# 20200805.net
KiCad netlist of a schematic drawn in Altium Designer
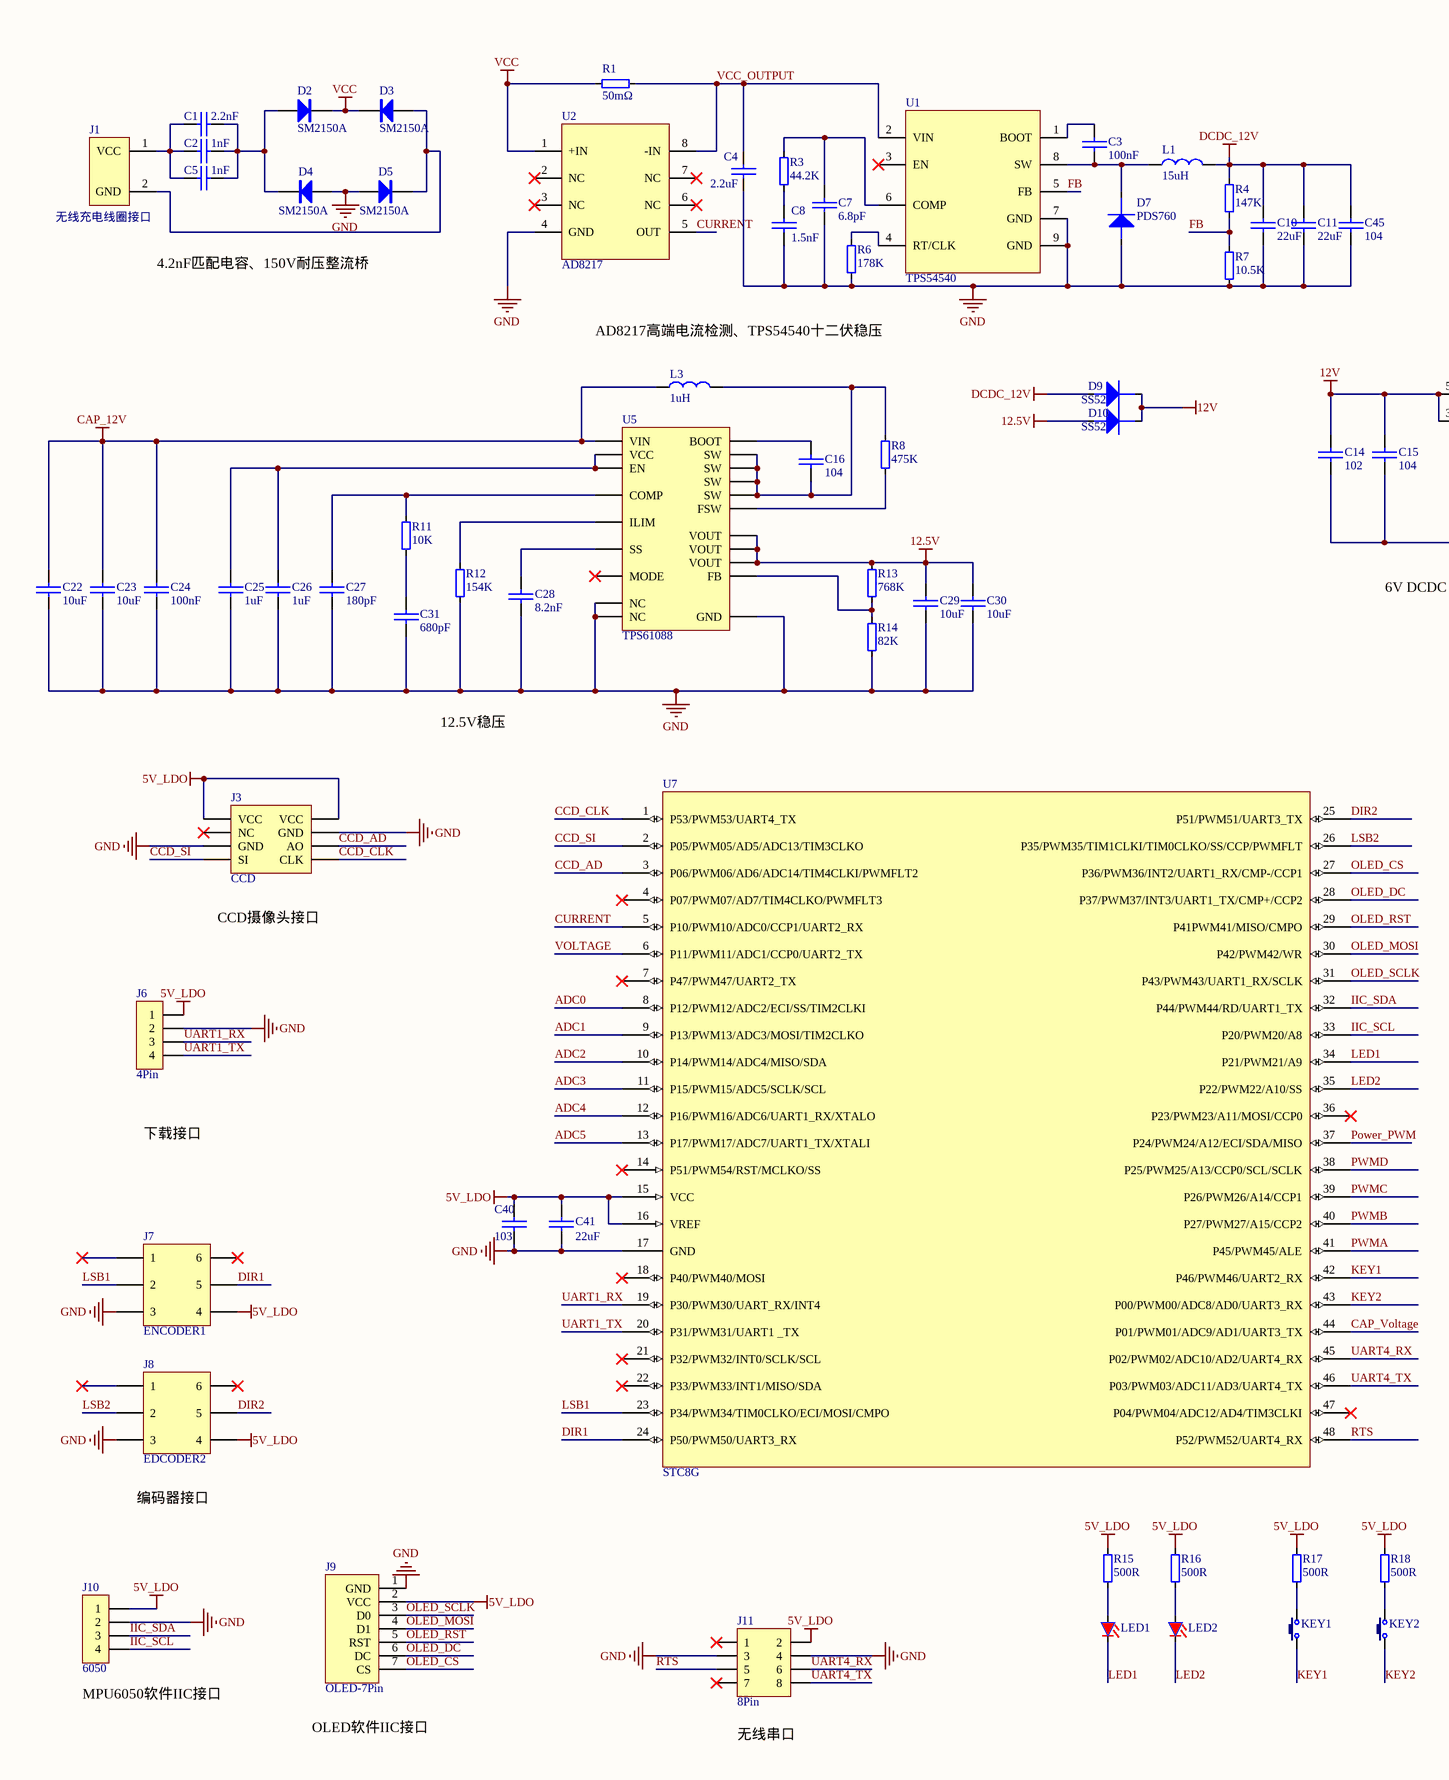
[diagram p0: 驰风队20200805.SchDoc, left]
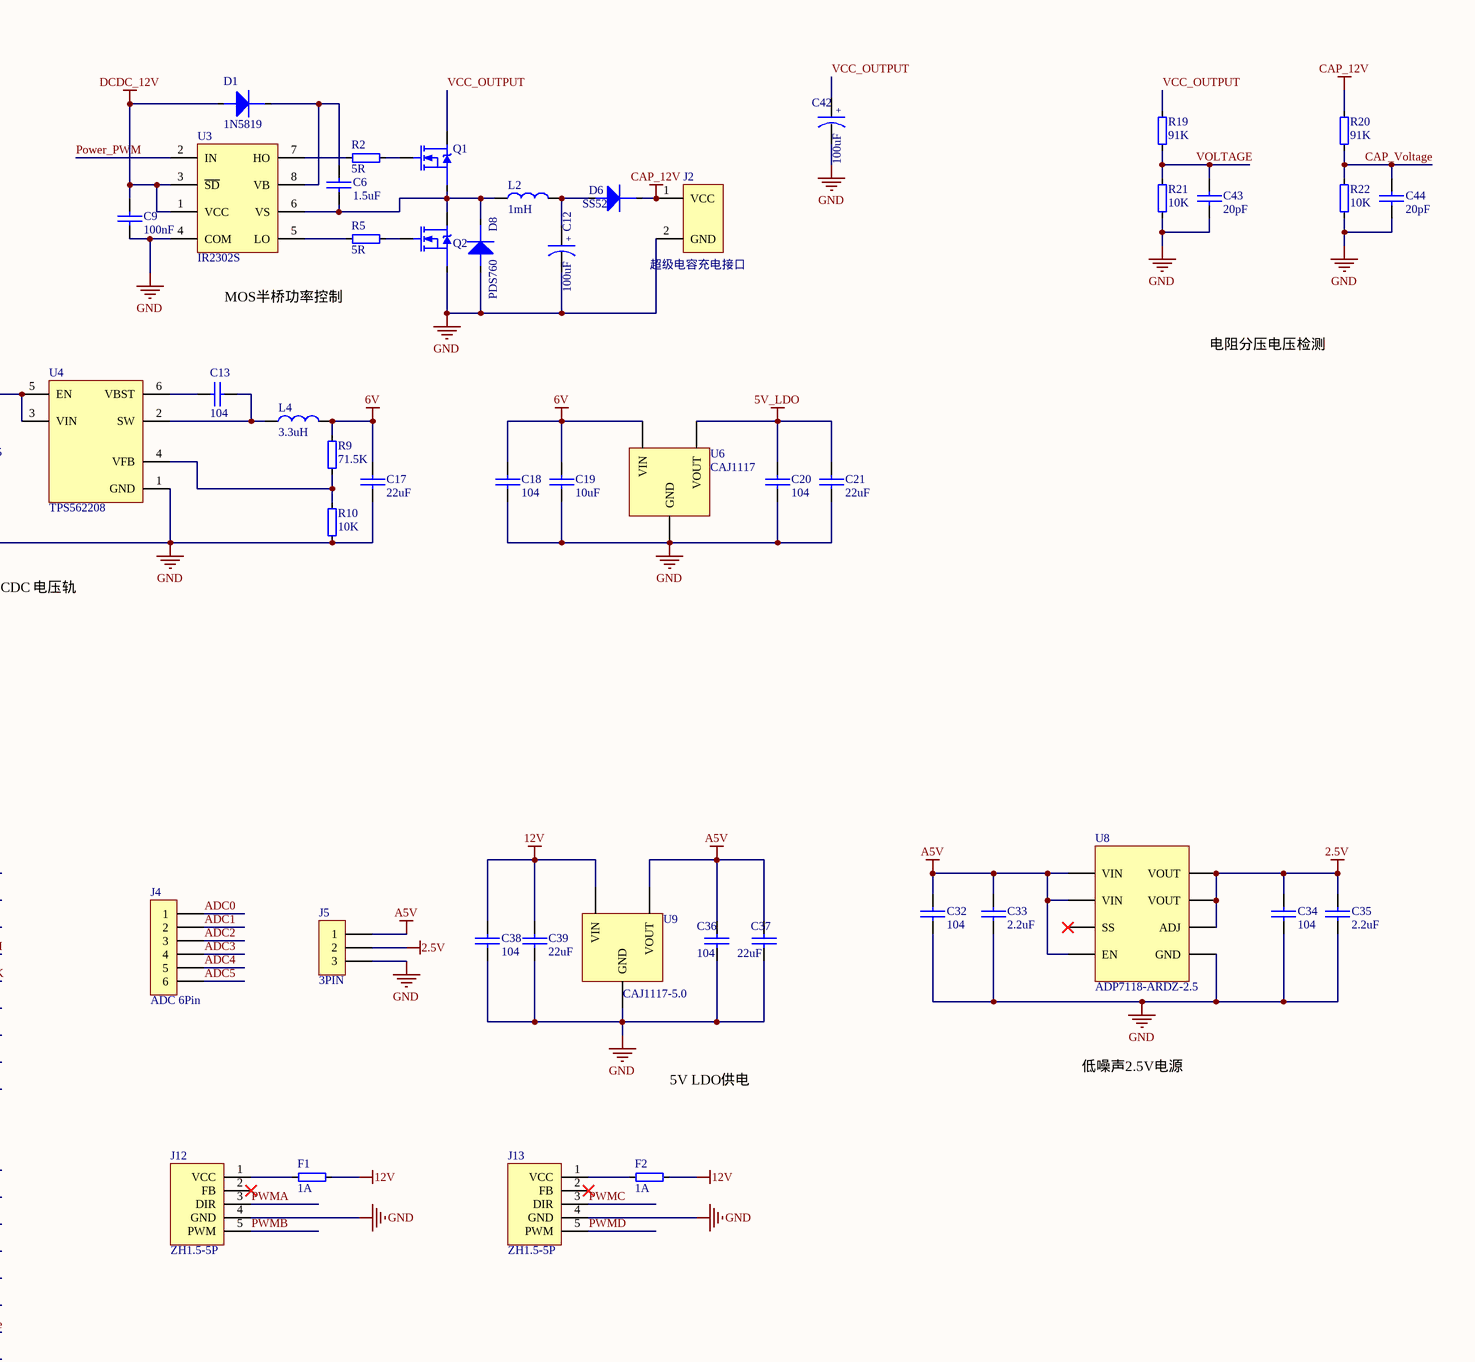
[diagram p1: 驰风队20200805.SchDoc, right]

(export (version "E")
  (design (tool "Eeschema 10.0.6"))
  (components
    (comp (ref "C1") (value "2.2nF") (footprint "C1206") (libsource (lib "PowerControl_v1") (part "MLCC")))
    (comp (ref "C2") (value "1nF") (footprint "C1206") (libsource (lib "PowerControl_v1") (part "MLCC")))
    (comp (ref "C3") (value "100nF") (footprint "C0603") (libsource (lib "PowerControl_v1") (part "MLCC")))
    (comp (ref "C4") (value "2.2uF") (footprint "C1206") (libsource (lib "PowerControl_v1") (part "MLCC")))
    (comp (ref "C5") (value "1nF") (footprint "C1206") (libsource (lib "PowerControl_v1") (part "MLCC")))
    (comp (ref "C6") (value "1.5uF") (footprint "C0603") (libsource (lib "PowerControl_v1") (part "MLCC")))
    (comp (ref "C7") (value "6.8pF") (footprint "C0603") (libsource (lib "PowerControl_v1") (part "MLCC")))
    (comp (ref "C8") (value "1.5nF") (footprint "C0603") (libsource (lib "PowerControl_v1") (part "MLCC")))
    (comp (ref "C9") (value "100nF") (footprint "C0603") (libsource (lib "PowerControl_v1") (part "MLCC")))
    (comp (ref "C10") (value "22uF") (footprint "C1206") (libsource (lib "PowerControl_v1") (part "MLCC")))
    (comp (ref "C11") (value "22uF") (footprint "C1206") (libsource (lib "PowerControl_v1") (part "MLCC")))
    (comp (ref "C12")
      (value "100uF")
      (footprint "CAP 8*9")
      (libsource (lib "PowerControl_v1") (part "BiCAP"))
    )
    (comp (ref "C13") (value "104") (footprint "C0603") (libsource (lib "MyLib") (part "MLCC")))
    (comp (ref "C14") (value "102") (footprint "C0603") (libsource (lib "MyLib") (part "MLCC")))
    (comp (ref "C15") (value "104") (footprint "C0603") (libsource (lib "MyLib") (part "MLCC")))
    (comp (ref "C16") (value "104") (footprint "C0603") (libsource (lib "PowerControl_v1") (part "MLCC")))
    (comp (ref "C17") (value "22uF") (footprint "C1206") (libsource (lib "MyLib") (part "MLCC")))
    (comp (ref "C18") (value "104") (footprint "C0603") (libsource (lib "MyLib") (part "MLCC")))
    (comp (ref "C19") (value "10uF") (footprint "C0603") (libsource (lib "MyLib") (part "MLCC")))
    (comp (ref "C20") (value "104") (footprint "C0603") (libsource (lib "MyLib") (part "MLCC")))
    (comp (ref "C21") (value "22uF") (footprint "C1206") (libsource (lib "MyLib") (part "MLCC")))
    (comp (ref "C22") (value "10uF") (footprint "C0603") (libsource (lib "PowerControl_v1") (part "MLCC")))
    (comp (ref "C23") (value "10uF") (footprint "C0603") (libsource (lib "PowerControl_v1") (part "MLCC")))
    (comp (ref "C24") (value "100nF") (footprint "C0603") (libsource (lib "PowerControl_v1") (part "MLCC")))
    (comp (ref "C25") (value "1uF") (footprint "C0603") (libsource (lib "PowerControl_v1") (part "MLCC")))
    (comp (ref "C26") (value "1uF") (footprint "C0603") (libsource (lib "PowerControl_v1") (part "MLCC")))
    (comp (ref "C27") (value "180pF") (footprint "C0603") (libsource (lib "PowerControl_v1") (part "MLCC")))
    (comp (ref "C28") (value "8.2nF") (footprint "C0603") (libsource (lib "PowerControl_v1") (part "MLCC")))
    (comp (ref "C29") (value "10uF") (footprint "C0603") (libsource (lib "PowerControl_v1") (part "MLCC")))
    (comp (ref "C30") (value "10uF") (footprint "C0603") (libsource (lib "PowerControl_v1") (part "MLCC")))
    (comp (ref "C31") (value "680pF") (footprint "C0603") (libsource (lib "PowerControl_v1") (part "MLCC")))
    (comp (ref "C32") (value "104") (footprint "C0603") (libsource (lib "PowerControl_v1") (part "MLCC")))
    (comp (ref "C33") (value "2.2uF") (footprint "C0603") (libsource (lib "PowerControl_v1") (part "MLCC")))
    (comp (ref "C34") (value "104") (footprint "C0603") (libsource (lib "PowerControl_v1") (part "MLCC")))
    (comp (ref "C35") (value "2.2uF") (footprint "C0603") (libsource (lib "PowerControl_v1") (part "MLCC")))
    (comp (ref "C36") (value "104") (footprint "C0603") (libsource (lib "PowerControl_v1") (part "MLCC")))
    (comp (ref "C37") (value "22uF") (footprint "C1206") (libsource (lib "PowerControl_v1") (part "MLCC")))
    (comp (ref "C38") (value "104") (footprint "C0603") (libsource (lib "PowerControl_v1") (part "MLCC")))
    (comp (ref "C39") (value "22uF") (footprint "C1206") (libsource (lib "PowerControl_v1") (part "MLCC")))
    (comp (ref "C40") (value "103") (footprint "C0603") (libsource (lib "PowerControl_v1") (part "MLCC")))
    (comp (ref "C41") (value "22uF") (footprint "C1206") (libsource (lib "MyLib") (part "MLCC")))
    (comp (ref "C42")
      (value "100uF")
      (footprint "CAP 8*9")
      (libsource (lib "PowerControl_v1") (part "BiCAP"))
    )
    (comp (ref "C43") (value "20pF") (footprint "C0603") (libsource (lib "PowerControl_v1") (part "MLCC")))
    (comp (ref "C44") (value "20pF") (footprint "C0603") (libsource (lib "PowerControl_v1") (part "MLCC")))
    (comp (ref "C45") (value "104") (footprint "C0603") (libsource (lib "MyLib") (part "MLCC")))
    (comp (ref "D1")
      (value "1N5819")
      (footprint "SOD123")
      (libsource (lib "PowerControl_v1") (part "1N5819"))
    )
    (comp (ref "D2")
      (value "SM2150A")
      (footprint "SMB")
      (description "肖特基二极管，150V耐压，2A工作电流")
      (libsource (lib "PowerControl_v1") (part "SM2150A"))
    )
    (comp (ref "D3")
      (value "SM2150A")
      (footprint "SMB")
      (description "肖特基二极管，150V耐压，2A工作电流")
      (libsource (lib "PowerControl_v1") (part "SM2150A"))
    )
    (comp (ref "D4")
      (value "SM2150A")
      (footprint "SMB")
      (description "肖特基二极管，150V耐压，2A工作电流")
      (libsource (lib "PowerControl_v1") (part "SM2150A"))
    )
    (comp (ref "D5")
      (value "SM2150A")
      (footprint "SMB")
      (description "肖特基二极管，150V耐压，2A工作电流")
      (libsource (lib "PowerControl_v1") (part "SM2150A"))
    )
    (comp (ref "D6") (value "SS52") (footprint "SMB") (libsource (lib "PowerControl_v1") (part "1N5819")))
    (comp (ref "D7")
      (value "PDS760")
      (footprint "PDS760")
      (libsource (lib "PowerControl_v1") (part "PDS760"))
    )
    (comp (ref "D8")
      (value "PDS760")
      (footprint "PDS760")
      (libsource (lib "PowerControl_v1") (part "PDS760"))
    )
    (comp (ref "D9") (value "SS52") (footprint "SMB") (libsource (lib "PowerControl_v1") (part "1N5819")))
    (comp (ref "D10") (value "SS52") (footprint "SMB") (libsource (lib "PowerControl_v1") (part "1N5819")))
    (comp (ref "F1") (value "1A") (footprint "R0805") (libsource (lib "MyLib") (part "RES")))
    (comp (ref "F2") (value "1A") (footprint "R0603") (libsource (lib "MyLib") (part "RES")))
    (comp (ref "J1") (value "无线充电线圈接口") (footprint "2P") (libsource (lib "") (part "2P_1")))
    (comp (ref "J2") (value "超级电容充电接口") (footprint "XT30") (libsource (lib "PowerControl_v1") (part "2P")))
    (comp (ref "J3") (value "CCD") (footprint "8Pin") (libsource (lib "MyLib") (part "CCD")))
    (comp (ref "J4")
      (value "ADC 6Pin")
      (footprint "ADC 6Pin")
      (libsource (lib "PowerControl_v1") (part "ADC 6Pin"))
    )
    (comp (ref "J5") (value "3PIN") (footprint "3PIN") (libsource (lib "PowerControl_v1") (part "3PIN")))
    (comp (ref "J6") (value "4Pin") (footprint "4Pin") (libsource (lib "PowerControl_v1") (part "4Pin")))
    (comp (ref "J7")
      (value "ENCODER1")
      (footprint "DC3 2*3P")
      (libsource (lib "PowerControl_v1") (part "DC3 2*3P"))
    )
    (comp (ref "J8")
      (value "EDCODER2")
      (footprint "DC3 2*3P")
      (libsource (lib "PowerControl_v1") (part "DC3 2*3P"))
    )
    (comp (ref "J9")
      (value "OLED-7Pin")
      (footprint "OLED-7Pin")
      (libsource (lib "PowerControl_v1") (part "OLED-7Pin"))
    )
    (comp (ref "J10") (value "6050") (footprint "4Pin") (libsource (lib "PowerControl_v1") (part "4Pin")))
    (comp (ref "J11") (value "8Pin") (footprint "8Pin") (libsource (lib "PowerControl_v1") (part "8Pin")))
    (comp (ref "J12") (value "ZH1.5-5P") (footprint "ZH1.5-5P") (libsource (lib "MyLib") (part "ZH1.5-5P")))
    (comp (ref "J13") (value "ZH1.5-5P") (footprint "ZH1.5-5P") (libsource (lib "MyLib") (part "ZH1.5-5P")))
    (comp (ref "KEY1") (value "KEY") (footprint "KEY") (libsource (lib "PowerControl_v1") (part "KEY")))
    (comp (ref "KEY2") (value "KEY") (footprint "KEY") (libsource (lib "PowerControl_v1") (part "KEY")))
    (comp (ref "L1") (value "15uH") (footprint "L13.5*12.5") (libsource (lib "PowerControl_v1") (part "LEN")))
    (comp (ref "L2") (value "1mH") (footprint "L13.5*12.5") (libsource (lib "PowerControl_v1") (part "LEN")))
    (comp (ref "L3") (value "1uH") (footprint "L0630") (libsource (lib "PowerControl_v1") (part "LEN")))
    (comp (ref "L4") (value "3.3uH") (footprint "L0630") (libsource (lib "MyLib") (part "LEN")))
    (comp (ref "LED1") (value "LED") (footprint "LED") (libsource (lib "PowerControl_v1") (part "LED")))
    (comp (ref "LED2") (value "LED") (footprint "LED") (libsource (lib "PowerControl_v1") (part "LED")))
    (comp (ref "Q1")
      (value "PSMN3R7-100BSE")
      (footprint "D2PAK")
      (description "100V耐压，3.5mΩ导通内阻")
      (libsource (lib "PowerControl_v1") (part "PSMN3R7-100BSE"))
    )
    (comp (ref "Q2")
      (value "PSMN3R7-100BSE")
      (footprint "D2PAK")
      (description "100V耐压，3.5mΩ导通内阻")
      (libsource (lib "PowerControl_v1") (part "PSMN3R7-100BSE"))
    )
    (comp (ref "R1") (value "50mΩ") (footprint "R2010") (libsource (lib "PowerControl_v1") (part "RES")))
    (comp (ref "R2") (value "5R") (footprint "R0603") (libsource (lib "PowerControl_v1") (part "RES")))
    (comp (ref "R3") (value "44.2K") (footprint "R0603") (libsource (lib "PowerControl_v1") (part "RES")))
    (comp (ref "R4") (value "147K") (footprint "R0603") (libsource (lib "PowerControl_v1") (part "RES")))
    (comp (ref "R5") (value "5R") (footprint "R0603") (libsource (lib "PowerControl_v1") (part "RES")))
    (comp (ref "R6") (value "178K") (footprint "R0603") (libsource (lib "PowerControl_v1") (part "RES")))
    (comp (ref "R7") (value "10.5K") (footprint "R0603") (libsource (lib "PowerControl_v1") (part "RES")))
    (comp (ref "R8") (value "475K") (footprint "R0603") (libsource (lib "PowerControl_v1") (part "RES")))
    (comp (ref "R9") (value "71.5K") (footprint "R0603") (libsource (lib "PowerControl_v1") (part "RES")))
    (comp (ref "R10") (value "10K") (footprint "R0603") (libsource (lib "PowerControl_v1") (part "RES")))
    (comp (ref "R11") (value "10K") (footprint "R0603") (libsource (lib "PowerControl_v1") (part "RES")))
    (comp (ref "R12") (value "154K") (footprint "R0603") (libsource (lib "PowerControl_v1") (part "RES")))
    (comp (ref "R13") (value "768K") (footprint "R0603") (libsource (lib "PowerControl_v1") (part "RES")))
    (comp (ref "R14") (value "82K") (footprint "R0603") (libsource (lib "PowerControl_v1") (part "RES")))
    (comp (ref "R15") (value "500R") (footprint "R0603") (libsource (lib "PowerControl_v1") (part "RES")))
    (comp (ref "R16") (value "500R") (footprint "R0603") (libsource (lib "PowerControl_v1") (part "RES")))
    (comp (ref "R17") (value "500R") (footprint "R0603") (libsource (lib "PowerControl_v1") (part "RES")))
    (comp (ref "R18") (value "500R") (footprint "R0603") (libsource (lib "PowerControl_v1") (part "RES")))
    (comp (ref "R19") (value "91K") (footprint "R0603") (libsource (lib "PowerControl_v1") (part "RES")))
    (comp (ref "R20") (value "91K") (footprint "R0603") (libsource (lib "PowerControl_v1") (part "RES")))
    (comp (ref "R21") (value "10K") (footprint "R0603") (libsource (lib "PowerControl_v1") (part "RES")))
    (comp (ref "R22") (value "10K") (footprint "R0603") (libsource (lib "PowerControl_v1") (part "RES")))
    (comp (ref "U1")
      (value "TPS54540")
      (footprint "TPS54540")
      (libsource (lib "PowerControl_v1") (part "TPS54540"))
    )
    (comp (ref "U2")
      (value "AD8217")
      (footprint "AD8217")
      (libsource (lib "PowerControl_v1") (part "AD8217"))
    )
    (comp (ref "U3")
      (value "IR2302S")
      (footprint "IR2302S")
      (libsource (lib "PowerControl_v1") (part "IR2302S"))
    )
    (comp (ref "U4") (value "TPS562208") (footprint "TPS562208") (libsource (lib "MyLib") (part "TPS562208")))
    (comp (ref "U5")
      (value "TPS61088")
      (footprint "TPS61088")
      (libsource (lib "PowerControl_v1") (part "TPS61088"))
    )
    (comp (ref "U6") (value "CAJ1117") (footprint "SOT-89") (libsource (lib "MyLib") (part "CAJ1117")))
    (comp (ref "U7") (value "STC8G") (footprint "LQFP48") (libsource (lib "PowerControl_v1") (part "STC8G")))
    (comp (ref "U8")
      (value "ADP7118-ARDZ-2.5")
      (footprint "SOP8")
      (libsource (lib "PowerControl_v1") (part "ADP7118-ARDZ"))
    )
    (comp (ref "U9")
      (value "CAJ1117-5.0")
      (footprint "SOT-89")
      (description "最大输入电压15V，最大工作电流1A")
      (libsource (lib "PowerControl_v1") (part "CAJ1117"))
    )
  )
  (nets
    (net (code "1") (name "/ADC0") (class "Default")
      (node (ref "J4") (pin "1") (pinfunction "1_1") (pintype "passive"))
      (node (ref "U7") (pin "8") (pinfunction "P12/PWM12/ADC2/ECI/SS/TIM2CLKI_8") (pintype "bidirectional"))
    )
    (net (code "2") (name "/ADC1") (class "Default")
      (node (ref "J4") (pin "2") (pinfunction "2_2") (pintype "passive"))
      (node (ref "U7") (pin "9") (pinfunction "P13/PWM13/ADC3/MOSI/TIM2CLKO_9") (pintype "bidirectional"))
    )
    (net (code "3") (name "/ADC2") (class "Default")
      (node (ref "J4") (pin "3") (pinfunction "3_3") (pintype "passive"))
      (node (ref "U7") (pin "10") (pinfunction "P14/PWM14/ADC4/MISO/SDA_10") (pintype "bidirectional"))
    )
    (net (code "4") (name "/ADC3") (class "Default")
      (node (ref "J4") (pin "4") (pinfunction "4_4") (pintype "passive"))
      (node (ref "U7") (pin "11") (pinfunction "P15/PWM15/ADC5/SCLK/SCL_11") (pintype "bidirectional"))
    )
    (net (code "5") (name "/ADC4") (class "Default")
      (node (ref "J4") (pin "5") (pinfunction "5_5") (pintype "passive"))
      (node (ref "U7") (pin "12") (pinfunction "P16/PWM16/ADC6/UART1_RX/XTALO_12") (pintype "bidirectional"))
    )
    (net (code "6") (name "/ADC5") (class "Default")
      (node (ref "J4") (pin "6") (pinfunction "6_6") (pintype "passive"))
      (node (ref "U7") (pin "13") (pinfunction "P17/PWM17/ADC7/UART1_TX/XTALI_13") (pintype "bidirectional"))
    )
    (net (code "7") (name "/CAP_Voltage") (class "Default")
      (node (ref "C44") (pin "1") (pinfunction "1_1") (pintype "passive"))
      (node (ref "R20") (pin "1") (pinfunction "1_1") (pintype "passive"))
      (node (ref "R22") (pin "2") (pinfunction "2_2") (pintype "passive"))
      (node (ref "U7") (pin "44") (pinfunction "P01/PWM01/ADC9/AD1/UART3_TX_44") (pintype "bidirectional"))
    )
    (net (code "8") (name "/CCD_AD") (class "Default")
      (node (ref "J3") (pin "6") (pinfunction "AO_6") (pintype "passive"))
      (node (ref "U7") (pin "3") (pinfunction "P06/PWM06/AD6/ADC14/TIM4CLKI/PWMFLT2_3") (pintype "bidirectional"))
    )
    (net (code "9") (name "/CCD_CLK") (class "Default")
      (node (ref "J3") (pin "8") (pinfunction "CLK_8") (pintype "passive"))
      (node (ref "U7") (pin "1") (pinfunction "P53/PWM53/UART4_TX_1") (pintype "bidirectional"))
    )
    (net (code "10") (name "/CCD_SI") (class "Default")
      (node (ref "J3") (pin "7") (pinfunction "SI_7") (pintype "passive"))
      (node (ref "U7") (pin "2") (pinfunction "P05/PWM05/AD5/ADC13/TIM3CLKO_2") (pintype "bidirectional"))
    )
    (net (code "11") (name "/CURRENT") (class "Default")
      (node (ref "U2") (pin "5") (pinfunction "OUT_5") (pintype "passive"))
      (node (ref "U7") (pin "5") (pinfunction "P10/PWM10/ADC0/CCP1/UART2_RX_5") (pintype "bidirectional"))
    )
    (net (code "12") (name "/DIR1") (class "Default")
      (node (ref "J7") (pin "5") (pinfunction "5_5") (pintype "passive"))
      (node (ref "U7") (pin "24") (pinfunction "P50/PWM50/UART3_RX_24") (pintype "bidirectional"))
    )
    (net (code "13") (name "/DIR2") (class "Default")
      (node (ref "J8") (pin "5") (pinfunction "5_5") (pintype "passive"))
      (node (ref "U7") (pin "25") (pinfunction "P51/PWM51/UART3_TX_25") (pintype "bidirectional"))
    )
    (net (code "14") (name "/FB") (class "Default")
      (node (ref "R4") (pin "1") (pinfunction "1_1") (pintype "passive"))
      (node (ref "R7") (pin "2") (pinfunction "2_2") (pintype "passive"))
      (node (ref "U1") (pin "5") (pinfunction "FB_5") (pintype "passive"))
    )
    (net (code "15") (name "/IIC_SCL") (class "Default")
      (node (ref "J10") (pin "4") (pinfunction "4_4") (pintype "passive"))
      (node (ref "U7") (pin "33") (pinfunction "P20/PWM20/A8_33") (pintype "bidirectional"))
    )
    (net (code "16") (name "/IIC_SDA") (class "Default")
      (node (ref "J10") (pin "3") (pinfunction "3_3") (pintype "passive"))
      (node (ref "U7") (pin "32") (pinfunction "P44/PWM44/RD/UART1_TX_32") (pintype "bidirectional"))
    )
    (net (code "17") (name "/KEY1") (class "Default")
      (node (ref "KEY1") (pin "1") (pinfunction "1_1") (pintype "passive"))
      (node (ref "U7") (pin "42") (pinfunction "P46/PWM46/UART2_RX_42") (pintype "bidirectional"))
    )
    (net (code "18") (name "/KEY2") (class "Default")
      (node (ref "KEY2") (pin "1") (pinfunction "1_1") (pintype "passive"))
      (node (ref "U7") (pin "43") (pinfunction "P00/PWM00/ADC8/AD0/UART3_RX_43") (pintype "bidirectional"))
    )
    (net (code "19") (name "/LED1") (class "Default")
      (node (ref "LED1") (pin "2") (pinfunction "k_2") (pintype "passive"))
      (node (ref "U7") (pin "34") (pinfunction "P21/PWM21/A9_34") (pintype "bidirectional"))
    )
    (net (code "20") (name "/LED2") (class "Default")
      (node (ref "LED2") (pin "2") (pinfunction "k_2") (pintype "passive"))
      (node (ref "U7") (pin "35") (pinfunction "P22/PWM22/A10/SS_35") (pintype "bidirectional"))
    )
    (net (code "21") (name "/LSB1") (class "Default")
      (node (ref "J7") (pin "2") (pinfunction "2_2") (pintype "passive"))
      (node (ref "U7") (pin "23") (pinfunction "P34/PWM34/TIM0CLKO/ECI/MOSI/CMPO_23") (pintype "bidirectional"))
    )
    (net (code "22") (name "/LSB2") (class "Default")
      (node (ref "J8") (pin "2") (pinfunction "2_2") (pintype "passive"))
      (node (ref "U7") (pin "26") (pinfunction "P35/PWM35/TIM1CLKI/TIM0CLKO/SS/CCP/PWMFLT_26") (pintype "bidirectional"))
    )
    (net (code "23") (name "/OLED_CS") (class "Default")
      (node (ref "J9") (pin "7") (pinfunction "CS_7") (pintype "passive"))
      (node (ref "U7") (pin "27") (pinfunction "P36/PWM36/INT2/UART1_RX/CMP-/CCP1_27") (pintype "bidirectional"))
    )
    (net (code "24") (name "/OLED_DC") (class "Default")
      (node (ref "J9") (pin "6") (pinfunction "DC_6") (pintype "passive"))
      (node (ref "U7") (pin "28") (pinfunction "P37/PWM37/INT3/UART1_TX/CMP+/CCP2_28") (pintype "bidirectional"))
    )
    (net (code "25") (name "/OLED_MOSI") (class "Default")
      (node (ref "J9") (pin "4") (pinfunction "D1_4") (pintype "passive"))
      (node (ref "U7") (pin "30") (pinfunction "P42/PWM42/WR_30") (pintype "bidirectional"))
    )
    (net (code "26") (name "/OLED_RST") (class "Default")
      (node (ref "J9") (pin "5") (pinfunction "RST_5") (pintype "passive"))
      (node (ref "U7") (pin "29") (pinfunction "P41PWM41/MISO/CMPO_29") (pintype "bidirectional"))
    )
    (net (code "27") (name "/OLED_SCLK") (class "Default")
      (node (ref "J9") (pin "3") (pinfunction "D0_3") (pintype "passive"))
      (node (ref "U7") (pin "31") (pinfunction "P43/PWM43/UART1_RX/SCLK_31") (pintype "bidirectional"))
    )
    (net (code "28") (name "/PWMA") (class "Default")
      (node (ref "J12") (pin "3") (pinfunction "DIR_3") (pintype "passive"))
      (node (ref "U7") (pin "41") (pinfunction "P45/PWM45/ALE_41") (pintype "bidirectional"))
    )
    (net (code "29") (name "/PWMB") (class "Default")
      (node (ref "J12") (pin "5") (pinfunction "PWM_5") (pintype "passive"))
      (node (ref "U7") (pin "40") (pinfunction "P27/PWM27/A15/CCP2_40") (pintype "bidirectional"))
    )
    (net (code "30") (name "/PWMC") (class "Default")
      (node (ref "J13") (pin "3") (pinfunction "DIR_3") (pintype "passive"))
      (node (ref "U7") (pin "39") (pinfunction "P26/PWM26/A14/CCP1_39") (pintype "bidirectional"))
    )
    (net (code "31") (name "/PWMD") (class "Default")
      (node (ref "J13") (pin "5") (pinfunction "PWM_5") (pintype "passive"))
      (node (ref "U7") (pin "38") (pinfunction "P25/PWM25/A13/CCP0/SCL/SCLK_38") (pintype "bidirectional"))
    )
    (net (code "32") (name "/Power_PWM") (class "Default")
      (node (ref "U3") (pin "2") (pinfunction "IN_2") (pintype "passive"))
      (node (ref "U7") (pin "37") (pinfunction "P24/PWM24/A12/ECI/SDA/MISO_37") (pintype "bidirectional"))
    )
    (net (code "33") (name "/RTS") (class "Default")
      (node (ref "J11") (pin "5") (pinfunction "5_5") (pintype "passive"))
      (node (ref "U7") (pin "48") (pinfunction "P52/PWM52/UART4_RX_48") (pintype "bidirectional"))
    )
    (net (code "34") (name "/UART1_RX") (class "Default")
      (node (ref "J6") (pin "3") (pinfunction "3_3") (pintype "passive"))
      (node (ref "U7") (pin "19") (pinfunction "P30/PWM30/UART_RX/INT4_19") (pintype "bidirectional"))
    )
    (net (code "35") (name "/UART1_TX") (class "Default")
      (node (ref "J6") (pin "4") (pinfunction "4_4") (pintype "passive"))
      (node (ref "U7") (pin "20") (pinfunction "P31/PWM31/UART1__TX_20") (pintype "bidirectional"))
    )
    (net (code "36") (name "/UART4_RX") (class "Default")
      (node (ref "J11") (pin "6") (pinfunction "6_6") (pintype "passive"))
      (node (ref "U7") (pin "45") (pinfunction "P02/PWM02/ADC10/AD2/UART4_RX_45") (pintype "bidirectional"))
    )
    (net (code "37") (name "/UART4_TX") (class "Default")
      (node (ref "J11") (pin "8") (pinfunction "8_8") (pintype "passive"))
      (node (ref "U7") (pin "46") (pinfunction "P03/PWM03/ADC11/AD3/UART4_TX_46") (pintype "bidirectional"))
    )
    (net (code "38") (name "/VCC_OUTPUT") (class "Default")
      (node (ref "C4") (pin "1") (pinfunction "1_1") (pintype "passive"))
      (node (ref "C42") (pin "1") (pinfunction "1_1") (pintype "passive"))
      (node (ref "Q1") (pin "2") (pinfunction "D_2") (pintype "passive"))
      (node (ref "R1") (pin "2") (pinfunction "2_2") (pintype "passive"))
      (node (ref "R19") (pin "2") (pinfunction "2_2") (pintype "passive"))
      (node (ref "U1") (pin "2") (pinfunction "VIN_2") (pintype "passive"))
      (node (ref "U2") (pin "8") (pinfunction "-IN_8") (pintype "passive"))
    )
    (net (code "39") (name "/VOLTAGE") (class "Default")
      (node (ref "C43") (pin "1") (pinfunction "1_1") (pintype "passive"))
      (node (ref "R19") (pin "1") (pinfunction "1_1") (pintype "passive"))
      (node (ref "R21") (pin "2") (pinfunction "2_2") (pintype "passive"))
      (node (ref "U7") (pin "6") (pinfunction "P11/PWM11/ADC1/CCP0/UART2_TX_6") (pintype "bidirectional"))
    )
    (net (code "40") (name "2.5V") (class "Default")
      (node (ref "C34") (pin "1") (pinfunction "1_1") (pintype "passive"))
      (node (ref "C35") (pin "1") (pinfunction "1_1") (pintype "passive"))
      (node (ref "J5") (pin "2") (pinfunction "2_2") (pintype "passive"))
      (node (ref "U8") (pin "1") (pinfunction "VOUT_1") (pintype "passive"))
      (node (ref "U8") (pin "2") (pinfunction "VOUT_2") (pintype "passive"))
      (node (ref "U8") (pin "3") (pinfunction "ADJ_3") (pintype "passive"))
    )
    (net (code "41") (name "5V_LDO") (class "Default")
      (node (ref "C20") (pin "2") (pinfunction "2_2") (pintype "passive"))
      (node (ref "C21") (pin "2") (pinfunction "2_2") (pintype "passive"))
      (node (ref "C40") (pin "1") (pinfunction "1_1") (pintype "passive"))
      (node (ref "C41") (pin "1") (pinfunction "1_1") (pintype "passive"))
      (node (ref "J10") (pin "1") (pinfunction "1_1") (pintype "passive"))
      (node (ref "J11") (pin "2") (pinfunction "2_2") (pintype "passive"))
      (node (ref "J3") (pin "1") (pinfunction "VCC_1") (pintype "passive"))
      (node (ref "J3") (pin "2") (pinfunction "VCC_2") (pintype "passive"))
      (node (ref "J6") (pin "1") (pinfunction "1_1") (pintype "passive"))
      (node (ref "J7") (pin "4") (pinfunction "4_4") (pintype "passive"))
      (node (ref "J8") (pin "4") (pinfunction "4_4") (pintype "passive"))
      (node (ref "J9") (pin "2") (pinfunction "VCC_2") (pintype "passive"))
      (node (ref "R15") (pin "2") (pinfunction "2_2") (pintype "passive"))
      (node (ref "R16") (pin "2") (pinfunction "2_2") (pintype "passive"))
      (node (ref "R17") (pin "2") (pinfunction "2_2") (pintype "passive"))
      (node (ref "R18") (pin "2") (pinfunction "2_2") (pintype "passive"))
      (node (ref "U6") (pin "2") (pinfunction "VOUT_2") (pintype "passive"))
      (node (ref "U7") (pin "15") (pinfunction "VCC_15") (pintype "input"))
      (node (ref "U7") (pin "16") (pinfunction "VREF_16") (pintype "input"))
    )
    (net (code "42") (name "6V") (class "Default")
      (node (ref "C17") (pin "1") (pinfunction "1_1") (pintype "passive"))
      (node (ref "C18") (pin "2") (pinfunction "2_2") (pintype "passive"))
      (node (ref "C19") (pin "2") (pinfunction "2_2") (pintype "passive"))
      (node (ref "L4") (pin "1") (pinfunction "1_1") (pintype "passive"))
      (node (ref "R9") (pin "2") (pinfunction "2_2") (pintype "passive"))
      (node (ref "U6") (pin "3") (pinfunction "VIN_3") (pintype "passive"))
    )
    (net (code "43") (name "12.5V") (class "Default")
      (node (ref "C29") (pin "1") (pinfunction "1_1") (pintype "passive"))
      (node (ref "C30") (pin "1") (pinfunction "1_1") (pintype "passive"))
      (node (ref "D10") (pin "1") (pinfunction "1_1") (pintype "passive"))
      (node (ref "R13") (pin "2") (pinfunction "2_2") (pintype "passive"))
      (node (ref "U5") (pin "14") (pinfunction "VOUT_14") (pintype "passive"))
      (node (ref "U5") (pin "15") (pinfunction "VOUT_15") (pintype "passive"))
      (node (ref "U5") (pin "16") (pinfunction "VOUT_16") (pintype "passive"))
    )
    (net (code "44") (name "12V") (class "Default")
      (node (ref "C14") (pin "1") (pinfunction "1_1") (pintype "passive"))
      (node (ref "C15") (pin "1") (pinfunction "1_1") (pintype "passive"))
      (node (ref "C38") (pin "2") (pinfunction "2_2") (pintype "passive"))
      (node (ref "C39") (pin "1") (pinfunction "1_1") (pintype "passive"))
      (node (ref "D10") (pin "2") (pinfunction "2_2") (pintype "passive"))
      (node (ref "D9") (pin "2") (pinfunction "2_2") (pintype "passive"))
      (node (ref "F1") (pin "2") (pinfunction "2_2") (pintype "passive"))
      (node (ref "F2") (pin "2") (pinfunction "2_2") (pintype "passive"))
      (node (ref "U4") (pin "3") (pinfunction "VIN_3") (pintype "passive"))
      (node (ref "U4") (pin "5") (pinfunction "EN_5") (pintype "passive"))
      (node (ref "U9") (pin "3") (pinfunction "VIN_3") (pintype "passive"))
    )
    (net (code "45") (name "A5V") (class "Default")
      (node (ref "C32") (pin "1") (pinfunction "1_1") (pintype "passive"))
      (node (ref "C33") (pin "1") (pinfunction "1_1") (pintype "passive"))
      (node (ref "C36") (pin "2") (pinfunction "2_2") (pintype "passive"))
      (node (ref "C37") (pin "1") (pinfunction "1_1") (pintype "passive"))
      (node (ref "J5") (pin "1") (pinfunction "1_1") (pintype "passive"))
      (node (ref "U8") (pin "5") (pinfunction "EN_5") (pintype "passive"))
      (node (ref "U8") (pin "7") (pinfunction "VIN_7") (pintype "passive"))
      (node (ref "U8") (pin "8") (pinfunction "VIN_8") (pintype "passive"))
      (node (ref "U9") (pin "2") (pinfunction "VOUT_2") (pintype "passive"))
    )
    (net (code "46") (name "CAP_12V") (class "Default")
      (node (ref "C22") (pin "2") (pinfunction "2_2") (pintype "passive"))
      (node (ref "C23") (pin "2") (pinfunction "2_2") (pintype "passive"))
      (node (ref "C24") (pin "2") (pinfunction "2_2") (pintype "passive"))
      (node (ref "D6") (pin "2") (pinfunction "2_2") (pintype "passive"))
      (node (ref "J2") (pin "1") (pinfunction "VCC_1") (pintype "passive"))
      (node (ref "L3") (pin "2") (pinfunction "2_2") (pintype "passive"))
      (node (ref "R20") (pin "2") (pinfunction "2_2") (pintype "passive"))
      (node (ref "U5") (pin "9") (pinfunction "VIN_9") (pintype "passive"))
    )
    (net (code "47") (name "DCDC_12V") (class "Default")
      (node (ref "C10") (pin "1") (pinfunction "1_1") (pintype "passive"))
      (node (ref "C11") (pin "1") (pinfunction "1_1") (pintype "passive"))
      (node (ref "C45") (pin "1") (pinfunction "1_1") (pintype "passive"))
      (node (ref "C9") (pin "1") (pinfunction "1_1") (pintype "passive"))
      (node (ref "D1") (pin "1") (pinfunction "1_1") (pintype "passive"))
      (node (ref "D9") (pin "1") (pinfunction "1_1") (pintype "passive"))
      (node (ref "L1") (pin "1") (pinfunction "1_1") (pintype "passive"))
      (node (ref "R4") (pin "2") (pinfunction "2_2") (pintype "passive"))
      (node (ref "U3") (pin "1") (pinfunction "VCC_1") (pintype "passive"))
      (node (ref "U3") (pin "3") (pinfunction "~{SD}_3") (pintype "passive"))
    )
    (net (code "48") (name "GND") (class "Default")
      (node (ref "C10") (pin "2") (pinfunction "2_2") (pintype "passive"))
      (node (ref "C11") (pin "2") (pinfunction "2_2") (pintype "passive"))
      (node (ref "C12") (pin "2") (pinfunction "2_2") (pintype "passive"))
      (node (ref "C14") (pin "2") (pinfunction "2_2") (pintype "passive"))
      (node (ref "C15") (pin "2") (pinfunction "2_2") (pintype "passive"))
      (node (ref "C17") (pin "2") (pinfunction "2_2") (pintype "passive"))
      (node (ref "C18") (pin "1") (pinfunction "1_1") (pintype "passive"))
      (node (ref "C19") (pin "1") (pinfunction "1_1") (pintype "passive"))
      (node (ref "C20") (pin "1") (pinfunction "1_1") (pintype "passive"))
      (node (ref "C21") (pin "1") (pinfunction "1_1") (pintype "passive"))
      (node (ref "C22") (pin "1") (pinfunction "1_1") (pintype "passive"))
      (node (ref "C23") (pin "1") (pinfunction "1_1") (pintype "passive"))
      (node (ref "C24") (pin "1") (pinfunction "1_1") (pintype "passive"))
      (node (ref "C25") (pin "1") (pinfunction "1_1") (pintype "passive"))
      (node (ref "C26") (pin "1") (pinfunction "1_1") (pintype "passive"))
      (node (ref "C27") (pin "1") (pinfunction "1_1") (pintype "passive"))
      (node (ref "C28") (pin "1") (pinfunction "1_1") (pintype "passive"))
      (node (ref "C29") (pin "2") (pinfunction "2_2") (pintype "passive"))
      (node (ref "C30") (pin "2") (pinfunction "2_2") (pintype "passive"))
      (node (ref "C31") (pin "1") (pinfunction "1_1") (pintype "passive"))
      (node (ref "C32") (pin "2") (pinfunction "2_2") (pintype "passive"))
      (node (ref "C33") (pin "2") (pinfunction "2_2") (pintype "passive"))
      (node (ref "C34") (pin "2") (pinfunction "2_2") (pintype "passive"))
      (node (ref "C35") (pin "2") (pinfunction "2_2") (pintype "passive"))
      (node (ref "C36") (pin "1") (pinfunction "1_1") (pintype "passive"))
      (node (ref "C37") (pin "2") (pinfunction "2_2") (pintype "passive"))
      (node (ref "C38") (pin "1") (pinfunction "1_1") (pintype "passive"))
      (node (ref "C39") (pin "2") (pinfunction "2_2") (pintype "passive"))
      (node (ref "C4") (pin "2") (pinfunction "2_2") (pintype "passive"))
      (node (ref "C40") (pin "2") (pinfunction "2_2") (pintype "passive"))
      (node (ref "C41") (pin "2") (pinfunction "2_2") (pintype "passive"))
      (node (ref "C42") (pin "2") (pinfunction "2_2") (pintype "passive"))
      (node (ref "C43") (pin "2") (pinfunction "2_2") (pintype "passive"))
      (node (ref "C44") (pin "2") (pinfunction "2_2") (pintype "passive"))
      (node (ref "C45") (pin "2") (pinfunction "2_2") (pintype "passive"))
      (node (ref "C7") (pin "2") (pinfunction "2_2") (pintype "passive"))
      (node (ref "C8") (pin "2") (pinfunction "2_2") (pintype "passive"))
      (node (ref "C9") (pin "2") (pinfunction "2_2") (pintype "passive"))
      (node (ref "D4") (pin "1") (pinfunction "A_1") (pintype "passive"))
      (node (ref "D5") (pin "1") (pinfunction "A_1") (pintype "passive"))
      (node (ref "D7") (pin "1") (pinfunction "A_1") (pintype "passive"))
      (node (ref "D8") (pin "1") (pinfunction "A_1") (pintype "passive"))
      (node (ref "J10") (pin "2") (pinfunction "2_2") (pintype "passive"))
      (node (ref "J11") (pin "3") (pinfunction "3_3") (pintype "passive"))
      (node (ref "J11") (pin "4") (pinfunction "4_4") (pintype "passive"))
      (node (ref "J12") (pin "4") (pinfunction "GND_4") (pintype "passive"))
      (node (ref "J13") (pin "4") (pinfunction "GND_4") (pintype "passive"))
      (node (ref "J2") (pin "2") (pinfunction "GND_2") (pintype "passive"))
      (node (ref "J3") (pin "4") (pinfunction "GND_4") (pintype "passive"))
      (node (ref "J3") (pin "5") (pinfunction "GND_5") (pintype "passive"))
      (node (ref "J5") (pin "3") (pinfunction "3_3") (pintype "passive"))
      (node (ref "J6") (pin "2") (pinfunction "2_2") (pintype "passive"))
      (node (ref "J7") (pin "3") (pinfunction "3_3") (pintype "passive"))
      (node (ref "J8") (pin "3") (pinfunction "3_3") (pintype "passive"))
      (node (ref "J9") (pin "1") (pinfunction "GND_1") (pintype "passive"))
      (node (ref "Q2") (pin "3") (pinfunction "S_3") (pintype "passive"))
      (node (ref "R10") (pin "1") (pinfunction "1_1") (pintype "passive"))
      (node (ref "R12") (pin "1") (pinfunction "1_1") (pintype "passive"))
      (node (ref "R14") (pin "1") (pinfunction "1_1") (pintype "passive"))
      (node (ref "R21") (pin "1") (pinfunction "1_1") (pintype "passive"))
      (node (ref "R22") (pin "1") (pinfunction "1_1") (pintype "passive"))
      (node (ref "R6") (pin "1") (pinfunction "1_1") (pintype "passive"))
      (node (ref "R7") (pin "1") (pinfunction "1_1") (pintype "passive"))
      (node (ref "U1") (pin "7") (pinfunction "GND_7") (pintype "passive"))
      (node (ref "U1") (pin "9") (pinfunction "GND_9") (pintype "passive"))
      (node (ref "U2") (pin "4") (pinfunction "GND_4") (pintype "passive"))
      (node (ref "U3") (pin "4") (pinfunction "COM_4") (pintype "passive"))
      (node (ref "U4") (pin "1") (pinfunction "GND_1") (pintype "passive"))
      (node (ref "U5") (pin "11") (pinfunction "NC_11") (pintype "passive"))
      (node (ref "U5") (pin "12") (pinfunction "NC_12") (pintype "passive"))
      (node (ref "U5") (pin "20") (pinfunction "GND_20") (pintype "passive"))
      (node (ref "U6") (pin "1") (pinfunction "GND_1") (pintype "passive"))
      (node (ref "U7") (pin "17") (pinfunction "GND_17") (pintype "passive"))
      (node (ref "U8") (pin "4") (pinfunction "GND_4") (pintype "passive"))
      (node (ref "U9") (pin "1") (pinfunction "GND_1") (pintype "passive"))
    )
    (net (code "49") (name "Net-(C8-Pad1)") (class "Default")
      (node (ref "C8") (pin "1") (pinfunction "1_1") (pintype "passive"))
      (node (ref "R3") (pin "1") (pinfunction "1_1") (pintype "passive"))
    )
    (net (code "50") (name "Net-(C12-Pad1)") (class "Default")
      (node (ref "C12") (pin "1") (pinfunction "1_1") (pintype "passive"))
      (node (ref "D6") (pin "1") (pinfunction "1_1") (pintype "passive"))
      (node (ref "L2") (pin "1") (pinfunction "1_1") (pintype "passive"))
    )
    (net (code "51") (name "Net-(C16-Pad2)") (class "Default")
      (node (ref "C16") (pin "2") (pinfunction "2_2") (pintype "passive"))
      (node (ref "L3") (pin "1") (pinfunction "1_1") (pintype "passive"))
      (node (ref "R8") (pin "2") (pinfunction "2_2") (pintype "passive"))
      (node (ref "U5") (pin "4") (pinfunction "SW_4") (pintype "passive"))
      (node (ref "U5") (pin "5") (pinfunction "SW_5") (pintype "passive"))
      (node (ref "U5") (pin "6") (pinfunction "SW_6") (pintype "passive"))
      (node (ref "U5") (pin "7") (pinfunction "SW_7") (pintype "passive"))
    )
    (net (code "52") (name "Net-(C31-Pad2)") (class "Default")
      (node (ref "C31") (pin "2") (pinfunction "2_2") (pintype "passive"))
      (node (ref "R11") (pin "1") (pinfunction "1_1") (pintype "passive"))
    )
    (net (code "53") (name "Net-(D2-A)") (class "Default")
      (node (ref "C1") (pin "1") (pinfunction "1_1") (pintype "passive"))
      (node (ref "C2") (pin "2") (pinfunction "2_2") (pintype "passive"))
      (node (ref "C5") (pin "2") (pinfunction "2_2") (pintype "passive"))
      (node (ref "D2") (pin "1") (pinfunction "A_1") (pintype "passive"))
      (node (ref "D4") (pin "2") (pinfunction "K_2") (pintype "passive"))
    )
    (net (code "54") (name "Net-(D3-A)") (class "Default")
      (node (ref "D3") (pin "1") (pinfunction "A_1") (pintype "passive"))
      (node (ref "D5") (pin "2") (pinfunction "K_2") (pintype "passive"))
      (node (ref "J1") (pin "2") (pinfunction "GND_2") (pintype "passive"))
    )
    (net (code "55") (name "Net-(D7-K)") (class "Default")
      (node (ref "C3") (pin "1") (pinfunction "1_1") (pintype "passive"))
      (node (ref "D7") (pin "2") (pinfunction "K_2") (pintype "passive"))
      (node (ref "L1") (pin "2") (pinfunction "2_2") (pintype "passive"))
      (node (ref "U1") (pin "8") (pinfunction "SW_8") (pintype "passive"))
    )
    (net (code "56") (name "Net-(D8-K)") (class "Default")
      (node (ref "C6") (pin "2") (pinfunction "2_2") (pintype "passive"))
      (node (ref "D8") (pin "2") (pinfunction "K_2") (pintype "passive"))
      (node (ref "L2") (pin "2") (pinfunction "2_2") (pintype "passive"))
      (node (ref "Q1") (pin "3") (pinfunction "S_3") (pintype "passive"))
      (node (ref "Q2") (pin "2") (pinfunction "D_2") (pintype "passive"))
      (node (ref "U3") (pin "6") (pinfunction "VS_6") (pintype "passive"))
    )
    (net (code "57") (name "Net-(J1-VCC)") (class "Default")
      (node (ref "C1") (pin "2") (pinfunction "2_2") (pintype "passive"))
      (node (ref "C2") (pin "1") (pinfunction "1_1") (pintype "passive"))
      (node (ref "C5") (pin "1") (pinfunction "1_1") (pintype "passive"))
      (node (ref "J1") (pin "1") (pinfunction "VCC_1") (pintype "passive"))
    )
    (net (code "58") (name "Net-(J12-VCC)") (class "Default")
      (node (ref "F1") (pin "1") (pinfunction "1_1") (pintype "passive"))
      (node (ref "J12") (pin "1") (pinfunction "VCC_1") (pintype "passive"))
    )
    (net (code "59") (name "Net-(J13-VCC)") (class "Default")
      (node (ref "F2") (pin "1") (pinfunction "1_1") (pintype "passive"))
      (node (ref "J13") (pin "1") (pinfunction "VCC_1") (pintype "passive"))
    )
    (net (code "60") (name "Net-(KEY1-Pad2)") (class "Default")
      (node (ref "KEY1") (pin "2") (pinfunction "2_2") (pintype "passive"))
      (node (ref "R17") (pin "1") (pinfunction "1_1") (pintype "passive"))
    )
    (net (code "61") (name "Net-(KEY2-Pad2)") (class "Default")
      (node (ref "KEY2") (pin "2") (pinfunction "2_2") (pintype "passive"))
      (node (ref "R18") (pin "1") (pinfunction "1_1") (pintype "passive"))
    )
    (net (code "62") (name "Net-(LED1-a)") (class "Default")
      (node (ref "LED1") (pin "1") (pinfunction "a_1") (pintype "passive"))
      (node (ref "R15") (pin "1") (pinfunction "1_1") (pintype "passive"))
    )
    (net (code "63") (name "Net-(LED2-a)") (class "Default")
      (node (ref "LED2") (pin "1") (pinfunction "a_1") (pintype "passive"))
      (node (ref "R16") (pin "1") (pinfunction "1_1") (pintype "passive"))
    )
    (net (code "64") (name "Net-(Q1-G)") (class "Default")
      (node (ref "Q1") (pin "1") (pinfunction "G_1") (pintype "passive"))
      (node (ref "R2") (pin "2") (pinfunction "2_2") (pintype "passive"))
    )
    (net (code "65") (name "Net-(Q2-G)") (class "Default")
      (node (ref "Q2") (pin "1") (pinfunction "G_1") (pintype "passive"))
      (node (ref "R5") (pin "2") (pinfunction "2_2") (pintype "passive"))
    )
    (net (code "66") (name "Net-(U1-BOOT)") (class "Default")
      (node (ref "C3") (pin "2") (pinfunction "2_2") (pintype "passive"))
      (node (ref "U1") (pin "1") (pinfunction "BOOT_1") (pintype "passive"))
    )
    (net (code "67") (name "Net-(U1-COMP)") (class "Default")
      (node (ref "C7") (pin "1") (pinfunction "1_1") (pintype "passive"))
      (node (ref "R3") (pin "2") (pinfunction "2_2") (pintype "passive"))
      (node (ref "U1") (pin "6") (pinfunction "COMP_6") (pintype "passive"))
    )
    (net (code "68") (name "Net-(U1-RT{slash}CLK)") (class "Default")
      (node (ref "R6") (pin "2") (pinfunction "2_2") (pintype "passive"))
      (node (ref "U1") (pin "4") (pinfunction "RT/CLK_4") (pintype "passive"))
    )
    (net (code "69") (name "Net-(U3-HO)") (class "Default")
      (node (ref "R2") (pin "1") (pinfunction "1_1") (pintype "passive"))
      (node (ref "U3") (pin "7") (pinfunction "HO_7") (pintype "passive"))
    )
    (net (code "70") (name "Net-(U3-LO)") (class "Default")
      (node (ref "R5") (pin "1") (pinfunction "1_1") (pintype "passive"))
      (node (ref "U3") (pin "5") (pinfunction "LO_5") (pintype "passive"))
    )
    (net (code "71") (name "Net-(U3-VB)") (class "Default")
      (node (ref "C6") (pin "1") (pinfunction "1_1") (pintype "passive"))
      (node (ref "D1") (pin "2") (pinfunction "2_2") (pintype "passive"))
      (node (ref "U3") (pin "8") (pinfunction "VB_8") (pintype "passive"))
    )
    (net (code "72") (name "Net-(U4-SW)") (class "Default")
      (node (ref "C13") (pin "2") (pinfunction "2_2") (pintype "passive"))
      (node (ref "L4") (pin "2") (pinfunction "2_2") (pintype "passive"))
      (node (ref "U4") (pin "2") (pinfunction "SW_2") (pintype "passive"))
    )
    (net (code "73") (name "Net-(U4-VBST)") (class "Default")
      (node (ref "C13") (pin "1") (pinfunction "1_1") (pintype "passive"))
      (node (ref "U4") (pin "6") (pinfunction "VBST_6") (pintype "passive"))
    )
    (net (code "74") (name "Net-(U4-VFB)") (class "Default")
      (node (ref "R10") (pin "2") (pinfunction "2_2") (pintype "passive"))
      (node (ref "R9") (pin "1") (pinfunction "1_1") (pintype "passive"))
      (node (ref "U4") (pin "4") (pinfunction "VFB_4") (pintype "passive"))
    )
    (net (code "75") (name "Net-(U5-BOOT)") (class "Default")
      (node (ref "C16") (pin "1") (pinfunction "1_1") (pintype "passive"))
      (node (ref "U5") (pin "8") (pinfunction "BOOT_8") (pintype "passive"))
    )
    (net (code "76") (name "Net-(U5-COMP)") (class "Default")
      (node (ref "C27") (pin "2") (pinfunction "2_2") (pintype "passive"))
      (node (ref "R11") (pin "2") (pinfunction "2_2") (pintype "passive"))
      (node (ref "U5") (pin "18") (pinfunction "COMP_18") (pintype "passive"))
    )
    (net (code "77") (name "Net-(U5-EN)") (class "Default")
      (node (ref "C25") (pin "2") (pinfunction "2_2") (pintype "passive"))
      (node (ref "C26") (pin "2") (pinfunction "2_2") (pintype "passive"))
      (node (ref "U5") (pin "1") (pinfunction "VCC_1") (pintype "passive"))
      (node (ref "U5") (pin "2") (pinfunction "EN_2") (pintype "passive"))
    )
    (net (code "78") (name "Net-(U5-FB)") (class "Default")
      (node (ref "R13") (pin "1") (pinfunction "1_1") (pintype "passive"))
      (node (ref "R14") (pin "2") (pinfunction "2_2") (pintype "passive"))
      (node (ref "U5") (pin "17") (pinfunction "FB_17") (pintype "passive"))
    )
    (net (code "79") (name "Net-(U5-FSW)") (class "Default")
      (node (ref "R8") (pin "1") (pinfunction "1_1") (pintype "passive"))
      (node (ref "U5") (pin "3") (pinfunction "FSW_3") (pintype "passive"))
    )
    (net (code "80") (name "Net-(U5-ILIM)") (class "Default")
      (node (ref "R12") (pin "2") (pinfunction "2_2") (pintype "passive"))
      (node (ref "U5") (pin "19") (pinfunction "ILIM_19") (pintype "passive"))
    )
    (net (code "81") (name "Net-(U5-SS)") (class "Default")
      (node (ref "C28") (pin "2") (pinfunction "2_2") (pintype "passive"))
      (node (ref "U5") (pin "10") (pinfunction "SS_10") (pintype "passive"))
    )
    (net (code "82") (name "VCC") (class "Default")
      (node (ref "D2") (pin "2") (pinfunction "K_2") (pintype "passive"))
      (node (ref "D3") (pin "2") (pinfunction "K_2") (pintype "passive"))
      (node (ref "R1") (pin "1") (pinfunction "1_1") (pintype "passive"))
      (node (ref "U2") (pin "1") (pinfunction "+IN_1") (pintype "passive"))
    )
    (net (code "83") (name "unconnected-(J3-NC-Pad3)") (class "Default")
      (node (ref "J3") (pin "3") (pinfunction "NC_3") (pintype "passive+no_connect"))
    )
    (net (code "84") (name "unconnected-(J7-Pad1)") (class "Default")
      (node (ref "J7") (pin "1") (pinfunction "1_1") (pintype "passive+no_connect"))
    )
    (net (code "85") (name "unconnected-(J7-Pad6)") (class "Default")
      (node (ref "J7") (pin "6") (pinfunction "6_6") (pintype "passive+no_connect"))
    )
    (net (code "86") (name "unconnected-(J8-Pad1)") (class "Default")
      (node (ref "J8") (pin "1") (pinfunction "1_1") (pintype "passive+no_connect"))
    )
    (net (code "87") (name "unconnected-(J8-Pad6)") (class "Default")
      (node (ref "J8") (pin "6") (pinfunction "6_6") (pintype "passive+no_connect"))
    )
    (net (code "88") (name "unconnected-(J11-Pad1)") (class "Default")
      (node (ref "J11") (pin "1") (pinfunction "1_1") (pintype "passive+no_connect"))
    )
    (net (code "89") (name "unconnected-(J11-Pad7)") (class "Default")
      (node (ref "J11") (pin "7") (pinfunction "7_7") (pintype "passive+no_connect"))
    )
    (net (code "90") (name "unconnected-(J12-FB-Pad2)") (class "Default")
      (node (ref "J12") (pin "2") (pinfunction "FB_2") (pintype "passive+no_connect"))
    )
    (net (code "91") (name "unconnected-(J13-FB-Pad2)") (class "Default")
      (node (ref "J13") (pin "2") (pinfunction "FB_2") (pintype "passive+no_connect"))
    )
    (net (code "92") (name "unconnected-(U1-EN-Pad3)") (class "Default")
      (node (ref "U1") (pin "3") (pinfunction "EN_3") (pintype "passive+no_connect"))
    )
    (net (code "93") (name "unconnected-(U2-NC-Pad2)") (class "Default")
      (node (ref "U2") (pin "2") (pinfunction "NC_2") (pintype "passive+no_connect"))
    )
    (net (code "94") (name "unconnected-(U2-NC-Pad3)") (class "Default")
      (node (ref "U2") (pin "3") (pinfunction "NC_3") (pintype "passive+no_connect"))
    )
    (net (code "95") (name "unconnected-(U2-NC-Pad6)") (class "Default")
      (node (ref "U2") (pin "6") (pinfunction "NC_6") (pintype "passive+no_connect"))
    )
    (net (code "96") (name "unconnected-(U2-NC-Pad7)") (class "Default")
      (node (ref "U2") (pin "7") (pinfunction "NC_7") (pintype "passive+no_connect"))
    )
    (net (code "97") (name "unconnected-(U5-MODE-Pad13)") (class "Default")
      (node (ref "U5") (pin "13") (pinfunction "MODE_13") (pintype "passive+no_connect"))
    )
    (net (code "98") (name "unconnected-(U7-P04{slash}PWM04{slash}ADC12{slash}AD4{slash}TIM3CLKI-Pad47)") (class "Default")
      (node (ref "U7") (pin "47") (pinfunction "P04/PWM04/ADC12/AD4/TIM3CLKI_47") (pintype "bidirectional+no_connect"))
    )
    (net (code "99") (name "unconnected-(U7-P07{slash}PWM07{slash}AD7{slash}TIM4CLKO{slash}PWMFLT3-Pad4)") (class "Default")
      (node (ref "U7") (pin "4") (pinfunction "P07/PWM07/AD7/TIM4CLKO/PWMFLT3_4") (pintype "bidirectional+no_connect"))
    )
    (net (code "100") (name "unconnected-(U7-P23{slash}PWM23{slash}A11{slash}MOSI{slash}CCP0-Pad36)") (class "Default")
      (node (ref "U7") (pin "36") (pinfunction "P23/PWM23/A11/MOSI/CCP0_36") (pintype "bidirectional+no_connect"))
    )
    (net (code "101") (name "unconnected-(U7-P32{slash}PWM32{slash}INT0{slash}SCLK{slash}SCL-Pad21)") (class "Default")
      (node (ref "U7") (pin "21") (pinfunction "P32/PWM32/INT0/SCLK/SCL_21") (pintype "bidirectional+no_connect"))
    )
    (net (code "102") (name "unconnected-(U7-P33{slash}PWM33{slash}INT1{slash}MISO{slash}SDA-Pad22)") (class "Default")
      (node (ref "U7") (pin "22") (pinfunction "P33/PWM33/INT1/MISO/SDA_22") (pintype "bidirectional+no_connect"))
    )
    (net (code "103") (name "unconnected-(U7-P40{slash}PWM40{slash}MOSI-Pad18)") (class "Default")
      (node (ref "U7") (pin "18") (pinfunction "P40/PWM40/MOSI_18") (pintype "bidirectional+no_connect"))
    )
    (net (code "104") (name "unconnected-(U7-P47{slash}PWM47{slash}UART2_TX-Pad7)") (class "Default")
      (node (ref "U7") (pin "7") (pinfunction "P47/PWM47/UART2_TX_7") (pintype "bidirectional+no_connect"))
    )
    (net (code "105") (name "unconnected-(U7-P51{slash}PWM54{slash}RST{slash}MCLKO{slash}SS-Pad14)") (class "Default")
      (node (ref "U7") (pin "14") (pinfunction "P51/PWM54/RST/MCLKO/SS_14") (pintype "input+no_connect"))
    )
    (net (code "106") (name "unconnected-(U8-SS-Pad6)") (class "Default")
      (node (ref "U8") (pin "6") (pinfunction "SS_6") (pintype "passive+no_connect"))
    )
  )
)
